# 2364_ROM-el_PLCC.net
KiCad netlist of a schematic drawn in EAGLE
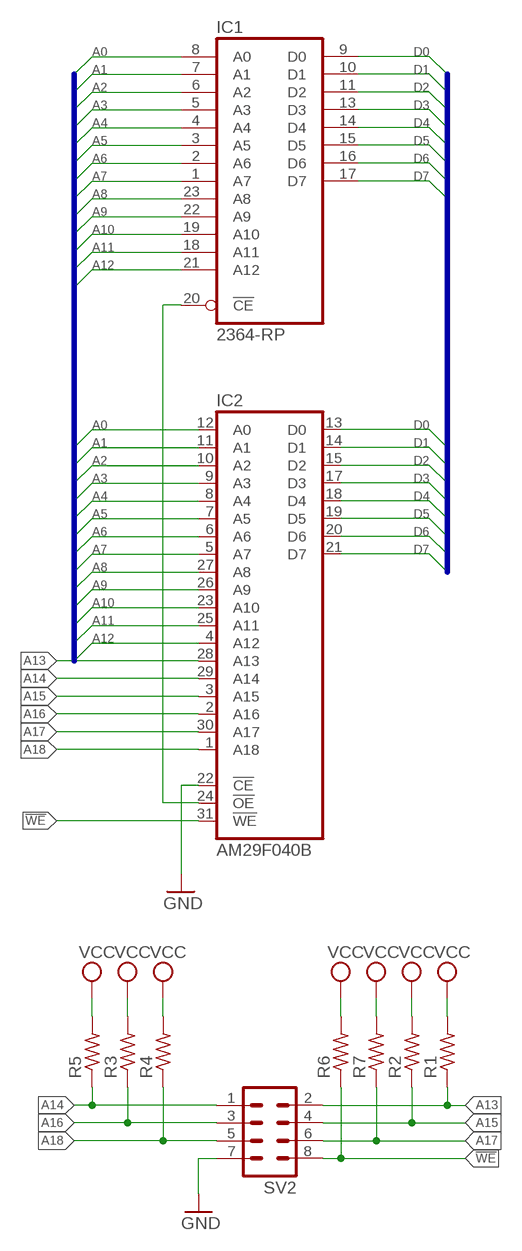
[diagram p0: schematic, sheet 1]

(export (version "E")
  (design (tool "Eeschema 10.0.6"))
  (components
    (comp (ref "IC1")
      (value "2364-RP")
      (footprint "eagle-import:DIL24-ROUNDPAD")
      (libsource (lib "eagle-import") (part "2364-RP"))
    )
    (comp (ref "IC2")
      (value "AM29F040B")
      (footprint "eagle-import:PLCC32R")
      (libsource (lib "eagle-import") (part "SST39SF040AN"))
    )
    (comp (ref "R1")
      (value "R-US_R0402")
      (footprint "eagle-import:R0402")
      (libsource (lib "eagle-import") (part "R-US_R0402"))
    )
    (comp (ref "R2")
      (value "R-US_R0402")
      (footprint "eagle-import:R0402")
      (libsource (lib "eagle-import") (part "R-US_R0402"))
    )
    (comp (ref "R3")
      (value "R-US_R0402")
      (footprint "eagle-import:R0402")
      (libsource (lib "eagle-import") (part "R-US_R0402"))
    )
    (comp (ref "R4")
      (value "R-US_R0402")
      (footprint "eagle-import:R0402")
      (libsource (lib "eagle-import") (part "R-US_R0402"))
    )
    (comp (ref "R5")
      (value "R-US_R0402")
      (footprint "eagle-import:R0402")
      (libsource (lib "eagle-import") (part "R-US_R0402"))
    )
    (comp (ref "R6")
      (value "R-US_R0402")
      (footprint "eagle-import:R0402")
      (libsource (lib "eagle-import") (part "R-US_R0402"))
    )
    (comp (ref "R7")
      (value "R-US_R0402")
      (footprint "eagle-import:R0402")
      (libsource (lib "eagle-import") (part "R-US_R0402"))
    )
    (comp (ref "SV2")
      (value "MA04-2")
      (footprint "eagle-import:MA04-2")
      (libsource (lib "eagle-import") (part "MA04-2"))
    )
  )
  (nets
    (net (code "1") (name "/A0") (class "Default")
      (node (ref "IC1") (pin "8") (pinfunction "A0_8") (pintype "bidirectional"))
      (node (ref "IC2") (pin "12") (pinfunction "A0_12") (pintype "input"))
    )
    (net (code "2") (name "/A1") (class "Default")
      (node (ref "IC1") (pin "7") (pinfunction "A1_7") (pintype "bidirectional"))
      (node (ref "IC2") (pin "11") (pinfunction "A1_11") (pintype "input"))
    )
    (net (code "3") (name "/A2") (class "Default")
      (node (ref "IC1") (pin "6") (pinfunction "A2_6") (pintype "bidirectional"))
      (node (ref "IC2") (pin "10") (pinfunction "A2_10") (pintype "input"))
    )
    (net (code "4") (name "/A3") (class "Default")
      (node (ref "IC1") (pin "5") (pinfunction "A3_5") (pintype "bidirectional"))
      (node (ref "IC2") (pin "9") (pinfunction "A3_9") (pintype "input"))
    )
    (net (code "5") (name "/A4") (class "Default")
      (node (ref "IC1") (pin "4") (pinfunction "A4_4") (pintype "bidirectional"))
      (node (ref "IC2") (pin "8") (pinfunction "A4_8") (pintype "input"))
    )
    (net (code "6") (name "/A5") (class "Default")
      (node (ref "IC1") (pin "3") (pinfunction "A5_3") (pintype "bidirectional"))
      (node (ref "IC2") (pin "7") (pinfunction "A5_7") (pintype "input"))
    )
    (net (code "7") (name "/A6") (class "Default")
      (node (ref "IC1") (pin "2") (pinfunction "A6_2") (pintype "bidirectional"))
      (node (ref "IC2") (pin "6") (pinfunction "A6_6") (pintype "input"))
    )
    (net (code "8") (name "/A7") (class "Default")
      (node (ref "IC1") (pin "1") (pinfunction "A7_1") (pintype "bidirectional"))
      (node (ref "IC2") (pin "5") (pinfunction "A7_5") (pintype "input"))
    )
    (net (code "9") (name "/A8") (class "Default")
      (node (ref "IC1") (pin "23") (pinfunction "A8_23") (pintype "bidirectional"))
      (node (ref "IC2") (pin "27") (pinfunction "A8_27") (pintype "input"))
    )
    (net (code "10") (name "/A9") (class "Default")
      (node (ref "IC1") (pin "22") (pinfunction "A9_22") (pintype "bidirectional"))
      (node (ref "IC2") (pin "26") (pinfunction "A9_26") (pintype "input"))
    )
    (net (code "11") (name "/A10") (class "Default")
      (node (ref "IC1") (pin "19") (pinfunction "A10_19") (pintype "bidirectional"))
      (node (ref "IC2") (pin "23") (pinfunction "A10_23") (pintype "input"))
    )
    (net (code "12") (name "/A11") (class "Default")
      (node (ref "IC1") (pin "18") (pinfunction "A11_18") (pintype "bidirectional"))
      (node (ref "IC2") (pin "25") (pinfunction "A11_25") (pintype "input"))
    )
    (net (code "13") (name "/A12") (class "Default")
      (node (ref "IC1") (pin "21") (pinfunction "A12_21") (pintype "bidirectional"))
      (node (ref "IC2") (pin "4") (pinfunction "A12_4") (pintype "input"))
    )
    (net (code "14") (name "/D0") (class "Default")
      (node (ref "IC1") (pin "9") (pinfunction "D0_9") (pintype "tri_state"))
      (node (ref "IC2") (pin "13") (pinfunction "D0_13") (pintype "bidirectional"))
    )
    (net (code "15") (name "/D1") (class "Default")
      (node (ref "IC1") (pin "10") (pinfunction "D1_10") (pintype "tri_state"))
      (node (ref "IC2") (pin "14") (pinfunction "D1_14") (pintype "bidirectional"))
    )
    (net (code "16") (name "/D2") (class "Default")
      (node (ref "IC1") (pin "11") (pinfunction "D2_11") (pintype "tri_state"))
      (node (ref "IC2") (pin "15") (pinfunction "D2_15") (pintype "bidirectional"))
    )
    (net (code "17") (name "/D3") (class "Default")
      (node (ref "IC1") (pin "13") (pinfunction "D3_13") (pintype "tri_state"))
      (node (ref "IC2") (pin "17") (pinfunction "D3_17") (pintype "bidirectional"))
    )
    (net (code "18") (name "/D4") (class "Default")
      (node (ref "IC1") (pin "14") (pinfunction "D4_14") (pintype "tri_state"))
      (node (ref "IC2") (pin "18") (pinfunction "D4_18") (pintype "bidirectional"))
    )
    (net (code "19") (name "/D5") (class "Default")
      (node (ref "IC1") (pin "15") (pinfunction "D5_15") (pintype "tri_state"))
      (node (ref "IC2") (pin "19") (pinfunction "D5_19") (pintype "bidirectional"))
    )
    (net (code "20") (name "/D6") (class "Default")
      (node (ref "IC1") (pin "16") (pinfunction "D6_16") (pintype "tri_state"))
      (node (ref "IC2") (pin "20") (pinfunction "D6_20") (pintype "bidirectional"))
    )
    (net (code "21") (name "/D7") (class "Default")
      (node (ref "IC1") (pin "17") (pinfunction "D7_17") (pintype "tri_state"))
      (node (ref "IC2") (pin "21") (pinfunction "D7_21") (pintype "bidirectional"))
    )
    (net (code "22") (name "/~{WE}") (class "Default")
      (node (ref "IC2") (pin "31") (pinfunction "~{WE}_31") (pintype "input"))
      (node (ref "R6") (pin "1") (pinfunction "1_1") (pintype "passive"))
      (node (ref "SV2") (pin "8") (pinfunction "8_8") (pintype "passive"))
    )
    (net (code "23") (name "A13") (class "Default")
      (node (ref "IC2") (pin "28") (pinfunction "A13_28") (pintype "input"))
      (node (ref "R1") (pin "1") (pinfunction "1_1") (pintype "passive"))
      (node (ref "SV2") (pin "2") (pinfunction "2_2") (pintype "passive"))
    )
    (net (code "24") (name "A14") (class "Default")
      (node (ref "IC2") (pin "29") (pinfunction "A14_29") (pintype "input"))
      (node (ref "R5") (pin "1") (pinfunction "1_1") (pintype "passive"))
      (node (ref "SV2") (pin "1") (pinfunction "1_1") (pintype "passive"))
    )
    (net (code "25") (name "A15") (class "Default")
      (node (ref "IC2") (pin "3") (pinfunction "A15_3") (pintype "input"))
      (node (ref "R2") (pin "1") (pinfunction "1_1") (pintype "passive"))
      (node (ref "SV2") (pin "4") (pinfunction "4_4") (pintype "passive"))
    )
    (net (code "26") (name "A16") (class "Default")
      (node (ref "IC2") (pin "2") (pinfunction "A16_2") (pintype "input"))
      (node (ref "R3") (pin "1") (pinfunction "1_1") (pintype "passive"))
      (node (ref "SV2") (pin "3") (pinfunction "3_3") (pintype "passive"))
    )
    (net (code "27") (name "A17") (class "Default")
      (node (ref "IC2") (pin "30") (pinfunction "A17_30") (pintype "input"))
      (node (ref "R7") (pin "1") (pinfunction "1_1") (pintype "passive"))
      (node (ref "SV2") (pin "6") (pinfunction "6_6") (pintype "passive"))
    )
    (net (code "28") (name "A18") (class "Default")
      (node (ref "IC2") (pin "1") (pinfunction "A18_1") (pintype "input"))
      (node (ref "R4") (pin "1") (pinfunction "1_1") (pintype "passive"))
      (node (ref "SV2") (pin "5") (pinfunction "5_5") (pintype "passive"))
    )
    (net (code "29") (name "GND") (class "Default")
      (node (ref "IC2") (pin "22") (pinfunction "~{CE}_22") (pintype "input"))
      (node (ref "SV2") (pin "7") (pinfunction "7_7") (pintype "passive"))
    )
    (net (code "30") (name "Net-(IC1A-~{CE})") (class "Default")
      (node (ref "IC1") (pin "20") (pinfunction "~{CE}_20") (pintype "input"))
      (node (ref "IC2") (pin "24") (pinfunction "~{OE}_24") (pintype "input"))
    )
    (net (code "31") (name "VCC") (class "Default")
      (node (ref "R1") (pin "2") (pinfunction "2_2") (pintype "passive"))
      (node (ref "R2") (pin "2") (pinfunction "2_2") (pintype "passive"))
      (node (ref "R3") (pin "2") (pinfunction "2_2") (pintype "passive"))
      (node (ref "R4") (pin "2") (pinfunction "2_2") (pintype "passive"))
      (node (ref "R5") (pin "2") (pinfunction "2_2") (pintype "passive"))
      (node (ref "R6") (pin "2") (pinfunction "2_2") (pintype "passive"))
      (node (ref "R7") (pin "2") (pinfunction "2_2") (pintype "passive"))
    )
  )
)
